# input_pull_up.net
KiCad netlist of a schematic drawn in EAGLE
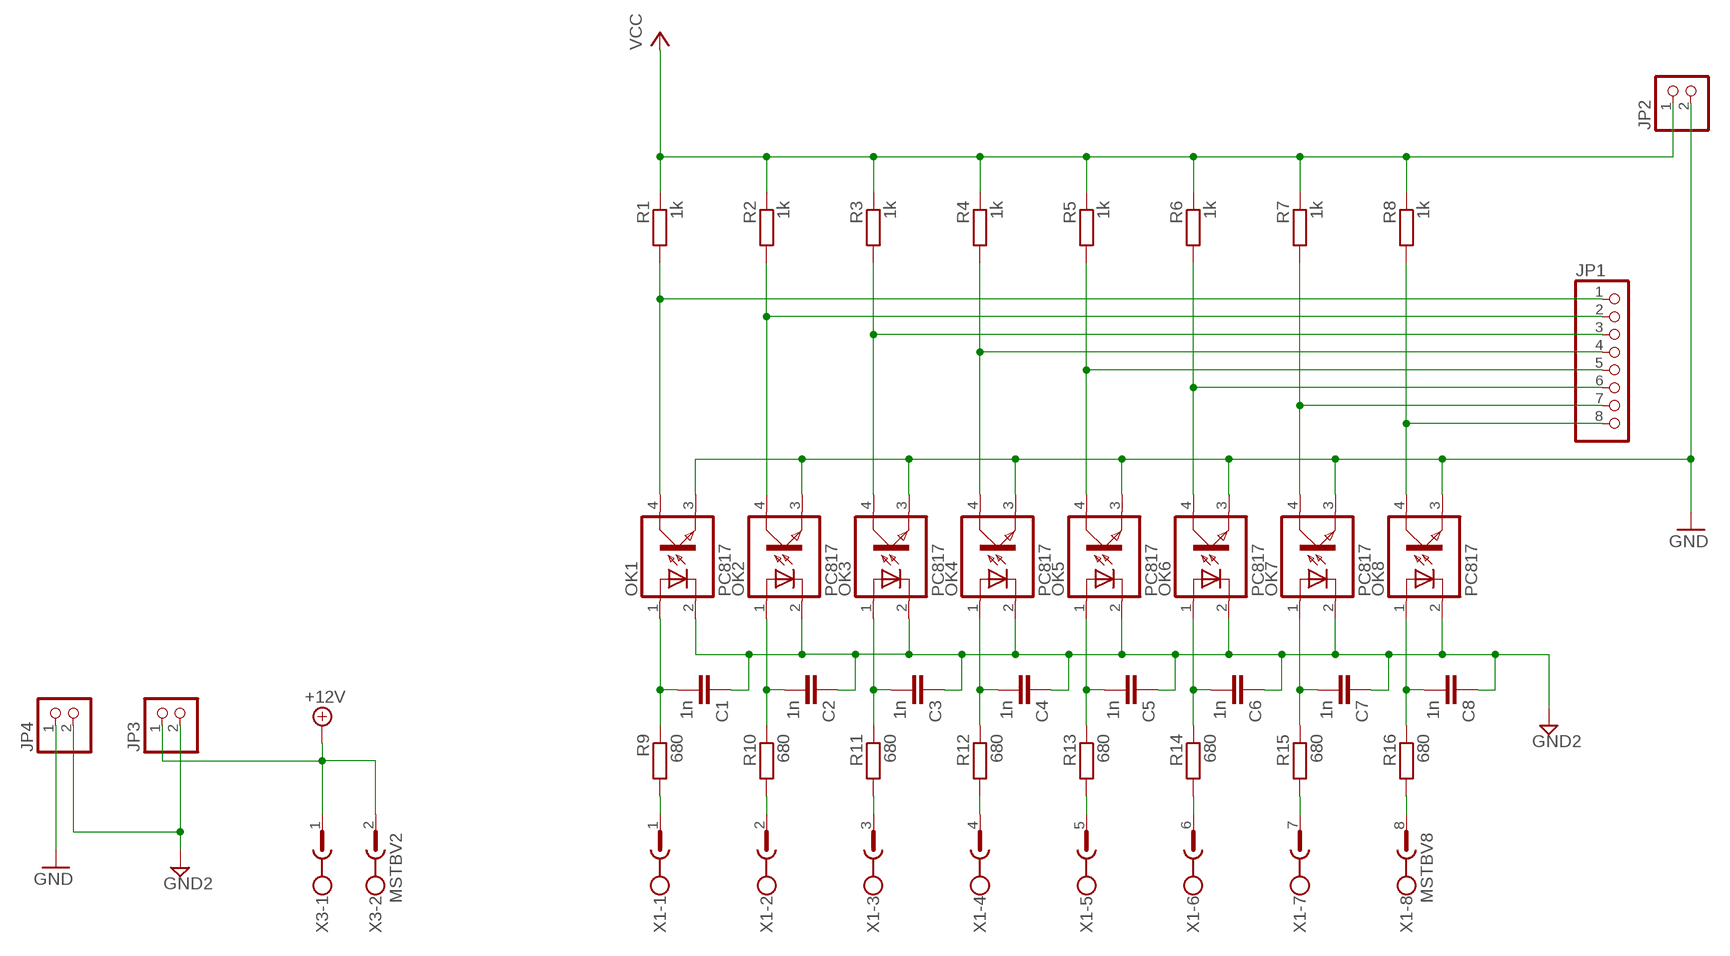
[diagram p0: schematic, sheet 1]

(export (version "E")
  (design (tool "Eeschema 10.0.6"))
  (components
    (comp (ref "C1")
      (value "1n")
      (footprint "eagle-import:C050-025X075")
      (libsource (lib "eagle-import") (part "C-EU050-025X075"))
    )
    (comp (ref "C2")
      (value "1n")
      (footprint "eagle-import:C050-025X075")
      (libsource (lib "eagle-import") (part "C-EU050-025X075"))
    )
    (comp (ref "C3")
      (value "1n")
      (footprint "eagle-import:C050-025X075")
      (libsource (lib "eagle-import") (part "C-EU050-025X075"))
    )
    (comp (ref "C4")
      (value "1n")
      (footprint "eagle-import:C050-025X075")
      (libsource (lib "eagle-import") (part "C-EU050-025X075"))
    )
    (comp (ref "C5")
      (value "1n")
      (footprint "eagle-import:C050-025X075")
      (libsource (lib "eagle-import") (part "C-EU050-025X075"))
    )
    (comp (ref "C6")
      (value "1n")
      (footprint "eagle-import:C050-025X075")
      (libsource (lib "eagle-import") (part "C-EU050-025X075"))
    )
    (comp (ref "C7")
      (value "1n")
      (footprint "eagle-import:C050-025X075")
      (libsource (lib "eagle-import") (part "C-EU050-025X075"))
    )
    (comp (ref "C8")
      (value "1n")
      (footprint "eagle-import:C050-025X075")
      (libsource (lib "eagle-import") (part "C-EU050-025X075"))
    )
    (comp (ref "JP1")
      (value "PINHD-1X8")
      (footprint "eagle-import:1X08")
      (libsource (lib "eagle-import") (part "PINHD-1X8"))
    )
    (comp (ref "JP2")
      (value "PINHD-1X2")
      (footprint "eagle-import:1X02")
      (libsource (lib "eagle-import") (part "PINHD-1X2"))
    )
    (comp (ref "JP3")
      (value "PINHD-1X2")
      (footprint "eagle-import:1X02")
      (libsource (lib "eagle-import") (part "PINHD-1X2"))
    )
    (comp (ref "JP4")
      (value "PINHD-1X2")
      (footprint "eagle-import:1X02")
      (libsource (lib "eagle-import") (part "PINHD-1X2"))
    )
    (comp (ref "OK1")
      (value "PC817")
      (footprint "eagle-import:DIL04")
      (fields (field (name "MPN") "PC817X4J000F"))
      (libsource (lib "eagle-import") (part "PC817"))
    )
    (comp (ref "OK2")
      (value "PC817")
      (footprint "eagle-import:DIL04")
      (fields (field (name "MPN") "PC817X4J000F"))
      (libsource (lib "eagle-import") (part "PC817"))
    )
    (comp (ref "OK3")
      (value "PC817")
      (footprint "eagle-import:DIL04")
      (fields (field (name "MPN") "PC817X4J000F"))
      (libsource (lib "eagle-import") (part "PC817"))
    )
    (comp (ref "OK4")
      (value "PC817")
      (footprint "eagle-import:DIL04")
      (fields (field (name "MPN") "PC817X4J000F"))
      (libsource (lib "eagle-import") (part "PC817"))
    )
    (comp (ref "OK5")
      (value "PC817")
      (footprint "eagle-import:DIL04")
      (fields (field (name "MPN") "PC817X4J000F"))
      (libsource (lib "eagle-import") (part "PC817"))
    )
    (comp (ref "OK6")
      (value "PC817")
      (footprint "eagle-import:DIL04")
      (fields (field (name "MPN") "PC817X4J000F"))
      (libsource (lib "eagle-import") (part "PC817"))
    )
    (comp (ref "OK7")
      (value "PC817")
      (footprint "eagle-import:DIL04")
      (fields (field (name "MPN") "PC817X4J000F"))
      (libsource (lib "eagle-import") (part "PC817"))
    )
    (comp (ref "OK8")
      (value "PC817")
      (footprint "eagle-import:DIL04")
      (fields (field (name "MPN") "PC817X4J000F"))
      (libsource (lib "eagle-import") (part "PC817"))
    )
    (comp (ref "R1")
      (value "1k")
      (footprint "eagle-import:0204_7")
      (libsource (lib "eagle-import") (part "R-EU_0204/7"))
    )
    (comp (ref "R2")
      (value "1k")
      (footprint "eagle-import:0204_7")
      (libsource (lib "eagle-import") (part "R-EU_0204/7"))
    )
    (comp (ref "R3")
      (value "1k")
      (footprint "eagle-import:0204_7")
      (libsource (lib "eagle-import") (part "R-EU_0204/7"))
    )
    (comp (ref "R4")
      (value "1k")
      (footprint "eagle-import:0204_7")
      (libsource (lib "eagle-import") (part "R-EU_0204/7"))
    )
    (comp (ref "R5")
      (value "1k")
      (footprint "eagle-import:0204_7")
      (libsource (lib "eagle-import") (part "R-EU_0204/7"))
    )
    (comp (ref "R6")
      (value "1k")
      (footprint "eagle-import:0204_7")
      (libsource (lib "eagle-import") (part "R-EU_0204/7"))
    )
    (comp (ref "R7")
      (value "1k")
      (footprint "eagle-import:0204_7")
      (libsource (lib "eagle-import") (part "R-EU_0204/7"))
    )
    (comp (ref "R8")
      (value "1k")
      (footprint "eagle-import:0204_7")
      (libsource (lib "eagle-import") (part "R-EU_0204/7"))
    )
    (comp (ref "R9")
      (value "680")
      (footprint "eagle-import:0204_7")
      (libsource (lib "eagle-import") (part "R-EU_0204/7"))
    )
    (comp (ref "R10")
      (value "680")
      (footprint "eagle-import:0204_7")
      (libsource (lib "eagle-import") (part "R-EU_0204/7"))
    )
    (comp (ref "R11")
      (value "680")
      (footprint "eagle-import:0204_7")
      (libsource (lib "eagle-import") (part "R-EU_0204/7"))
    )
    (comp (ref "R12")
      (value "680")
      (footprint "eagle-import:0204_7")
      (libsource (lib "eagle-import") (part "R-EU_0204/7"))
    )
    (comp (ref "R13")
      (value "680")
      (footprint "eagle-import:0204_7")
      (libsource (lib "eagle-import") (part "R-EU_0204/7"))
    )
    (comp (ref "R14")
      (value "680")
      (footprint "eagle-import:0204_7")
      (libsource (lib "eagle-import") (part "R-EU_0204/7"))
    )
    (comp (ref "R15")
      (value "680")
      (footprint "eagle-import:0204_7")
      (libsource (lib "eagle-import") (part "R-EU_0204/7"))
    )
    (comp (ref "R16")
      (value "680")
      (footprint "eagle-import:0204_7")
      (libsource (lib "eagle-import") (part "R-EU_0204/7"))
    )
    (comp (ref "X1")
      (value "MSTBV8")
      (footprint "eagle-import:MSTBV8")
      (libsource (lib "eagle-import") (part "MSTBV8"))
    )
    (comp (ref "X3")
      (value "MSTBV2")
      (footprint "eagle-import:MSTBV2")
      (libsource (lib "eagle-import") (part "MSTBV2"))
    )
  )
  (nets
    (net (code "1") (name "+12V") (class "Default")
      (node (ref "JP3") (pin "1") (pinfunction "1_1") (pintype "passive"))
      (node (ref "X3") (pin "1") (pinfunction "1_1") (pintype "passive"))
      (node (ref "X3") (pin "2") (pinfunction "1_2") (pintype "passive"))
    )
    (net (code "2") (name "GND") (class "Default")
      (node (ref "JP2") (pin "2") (pinfunction "2_2") (pintype "passive"))
      (node (ref "JP4") (pin "1") (pinfunction "1_1") (pintype "passive"))
      (node (ref "OK1") (pin "3") (pinfunction "EMIT_3") (pintype "passive"))
      (node (ref "OK2") (pin "3") (pinfunction "EMIT_3") (pintype "passive"))
      (node (ref "OK3") (pin "3") (pinfunction "EMIT_3") (pintype "passive"))
      (node (ref "OK4") (pin "3") (pinfunction "EMIT_3") (pintype "passive"))
      (node (ref "OK5") (pin "3") (pinfunction "EMIT_3") (pintype "passive"))
      (node (ref "OK6") (pin "3") (pinfunction "EMIT_3") (pintype "passive"))
      (node (ref "OK7") (pin "3") (pinfunction "EMIT_3") (pintype "passive"))
      (node (ref "OK8") (pin "3") (pinfunction "EMIT_3") (pintype "passive"))
    )
    (net (code "3") (name "GND2") (class "Default")
      (node (ref "C1") (pin "1") (pinfunction "1_1") (pintype "passive"))
      (node (ref "C2") (pin "1") (pinfunction "1_1") (pintype "passive"))
      (node (ref "C3") (pin "1") (pinfunction "1_1") (pintype "passive"))
      (node (ref "C4") (pin "1") (pinfunction "1_1") (pintype "passive"))
      (node (ref "C5") (pin "1") (pinfunction "1_1") (pintype "passive"))
      (node (ref "C6") (pin "1") (pinfunction "1_1") (pintype "passive"))
      (node (ref "C7") (pin "1") (pinfunction "1_1") (pintype "passive"))
      (node (ref "C8") (pin "1") (pinfunction "1_1") (pintype "passive"))
      (node (ref "JP3") (pin "2") (pinfunction "2_2") (pintype "passive"))
      (node (ref "JP4") (pin "2") (pinfunction "2_2") (pintype "passive"))
      (node (ref "OK1") (pin "2") (pinfunction "C_2") (pintype "passive"))
      (node (ref "OK2") (pin "2") (pinfunction "C_2") (pintype "passive"))
      (node (ref "OK3") (pin "2") (pinfunction "C_2") (pintype "passive"))
      (node (ref "OK4") (pin "2") (pinfunction "C_2") (pintype "passive"))
      (node (ref "OK5") (pin "2") (pinfunction "C_2") (pintype "passive"))
      (node (ref "OK6") (pin "2") (pinfunction "C_2") (pintype "passive"))
      (node (ref "OK7") (pin "2") (pinfunction "C_2") (pintype "passive"))
      (node (ref "OK8") (pin "2") (pinfunction "C_2") (pintype "passive"))
    )
    (net (code "4") (name "Net-(OK1-A)") (class "Default")
      (node (ref "C1") (pin "2") (pinfunction "2_2") (pintype "passive"))
      (node (ref "OK1") (pin "1") (pinfunction "A_1") (pintype "passive"))
      (node (ref "R9") (pin "1") (pinfunction "1_1") (pintype "passive"))
    )
    (net (code "5") (name "Net-(OK1-COL)") (class "Default")
      (node (ref "JP1") (pin "1") (pinfunction "1_1") (pintype "passive"))
      (node (ref "OK1") (pin "4") (pinfunction "COL_4") (pintype "passive"))
      (node (ref "R1") (pin "2") (pinfunction "2_2") (pintype "passive"))
    )
    (net (code "6") (name "Net-(OK2-A)") (class "Default")
      (node (ref "C2") (pin "2") (pinfunction "2_2") (pintype "passive"))
      (node (ref "OK2") (pin "1") (pinfunction "A_1") (pintype "passive"))
      (node (ref "R10") (pin "1") (pinfunction "1_1") (pintype "passive"))
    )
    (net (code "7") (name "Net-(OK2-COL)") (class "Default")
      (node (ref "JP1") (pin "2") (pinfunction "2_2") (pintype "passive"))
      (node (ref "OK2") (pin "4") (pinfunction "COL_4") (pintype "passive"))
      (node (ref "R2") (pin "2") (pinfunction "2_2") (pintype "passive"))
    )
    (net (code "8") (name "Net-(OK3-A)") (class "Default")
      (node (ref "C3") (pin "2") (pinfunction "2_2") (pintype "passive"))
      (node (ref "OK3") (pin "1") (pinfunction "A_1") (pintype "passive"))
      (node (ref "R11") (pin "1") (pinfunction "1_1") (pintype "passive"))
    )
    (net (code "9") (name "Net-(OK3-COL)") (class "Default")
      (node (ref "JP1") (pin "3") (pinfunction "3_3") (pintype "passive"))
      (node (ref "OK3") (pin "4") (pinfunction "COL_4") (pintype "passive"))
      (node (ref "R3") (pin "2") (pinfunction "2_2") (pintype "passive"))
    )
    (net (code "10") (name "Net-(OK4-A)") (class "Default")
      (node (ref "C4") (pin "2") (pinfunction "2_2") (pintype "passive"))
      (node (ref "OK4") (pin "1") (pinfunction "A_1") (pintype "passive"))
      (node (ref "R12") (pin "1") (pinfunction "1_1") (pintype "passive"))
    )
    (net (code "11") (name "Net-(OK4-COL)") (class "Default")
      (node (ref "JP1") (pin "4") (pinfunction "4_4") (pintype "passive"))
      (node (ref "OK4") (pin "4") (pinfunction "COL_4") (pintype "passive"))
      (node (ref "R4") (pin "2") (pinfunction "2_2") (pintype "passive"))
    )
    (net (code "12") (name "Net-(OK5-A)") (class "Default")
      (node (ref "C5") (pin "2") (pinfunction "2_2") (pintype "passive"))
      (node (ref "OK5") (pin "1") (pinfunction "A_1") (pintype "passive"))
      (node (ref "R13") (pin "1") (pinfunction "1_1") (pintype "passive"))
    )
    (net (code "13") (name "Net-(OK5-COL)") (class "Default")
      (node (ref "JP1") (pin "5") (pinfunction "5_5") (pintype "passive"))
      (node (ref "OK5") (pin "4") (pinfunction "COL_4") (pintype "passive"))
      (node (ref "R5") (pin "2") (pinfunction "2_2") (pintype "passive"))
    )
    (net (code "14") (name "Net-(OK6-A)") (class "Default")
      (node (ref "C6") (pin "2") (pinfunction "2_2") (pintype "passive"))
      (node (ref "OK6") (pin "1") (pinfunction "A_1") (pintype "passive"))
      (node (ref "R14") (pin "1") (pinfunction "1_1") (pintype "passive"))
    )
    (net (code "15") (name "Net-(OK6-COL)") (class "Default")
      (node (ref "JP1") (pin "6") (pinfunction "6_6") (pintype "passive"))
      (node (ref "OK6") (pin "4") (pinfunction "COL_4") (pintype "passive"))
      (node (ref "R6") (pin "2") (pinfunction "2_2") (pintype "passive"))
    )
    (net (code "16") (name "Net-(OK7-A)") (class "Default")
      (node (ref "C7") (pin "2") (pinfunction "2_2") (pintype "passive"))
      (node (ref "OK7") (pin "1") (pinfunction "A_1") (pintype "passive"))
      (node (ref "R15") (pin "1") (pinfunction "1_1") (pintype "passive"))
    )
    (net (code "17") (name "Net-(OK7-COL)") (class "Default")
      (node (ref "JP1") (pin "7") (pinfunction "7_7") (pintype "passive"))
      (node (ref "OK7") (pin "4") (pinfunction "COL_4") (pintype "passive"))
      (node (ref "R7") (pin "2") (pinfunction "2_2") (pintype "passive"))
    )
    (net (code "18") (name "Net-(OK8-A)") (class "Default")
      (node (ref "C8") (pin "2") (pinfunction "2_2") (pintype "passive"))
      (node (ref "OK8") (pin "1") (pinfunction "A_1") (pintype "passive"))
      (node (ref "R16") (pin "1") (pinfunction "1_1") (pintype "passive"))
    )
    (net (code "19") (name "Net-(OK8-COL)") (class "Default")
      (node (ref "JP1") (pin "8") (pinfunction "8_8") (pintype "passive"))
      (node (ref "OK8") (pin "4") (pinfunction "COL_4") (pintype "passive"))
      (node (ref "R8") (pin "2") (pinfunction "2_2") (pintype "passive"))
    )
    (net (code "20") (name "Net-(R9-Pad2)") (class "Default")
      (node (ref "R9") (pin "2") (pinfunction "2_2") (pintype "passive"))
      (node (ref "X1") (pin "1") (pinfunction "1_1") (pintype "passive"))
    )
    (net (code "21") (name "Net-(X1B-1)") (class "Default")
      (node (ref "R10") (pin "2") (pinfunction "2_2") (pintype "passive"))
      (node (ref "X1") (pin "2") (pinfunction "1_2") (pintype "passive"))
    )
    (net (code "22") (name "Net-(X1C-1)") (class "Default")
      (node (ref "R11") (pin "2") (pinfunction "2_2") (pintype "passive"))
      (node (ref "X1") (pin "3") (pinfunction "1_3") (pintype "passive"))
    )
    (net (code "23") (name "Net-(X1D-1)") (class "Default")
      (node (ref "R12") (pin "2") (pinfunction "2_2") (pintype "passive"))
      (node (ref "X1") (pin "4") (pinfunction "1_4") (pintype "passive"))
    )
    (net (code "24") (name "Net-(X1E-1)") (class "Default")
      (node (ref "R13") (pin "2") (pinfunction "2_2") (pintype "passive"))
      (node (ref "X1") (pin "5") (pinfunction "1_5") (pintype "passive"))
    )
    (net (code "25") (name "Net-(X1F-1)") (class "Default")
      (node (ref "R14") (pin "2") (pinfunction "2_2") (pintype "passive"))
      (node (ref "X1") (pin "6") (pinfunction "1_6") (pintype "passive"))
    )
    (net (code "26") (name "Net-(X1G-1)") (class "Default")
      (node (ref "R15") (pin "2") (pinfunction "2_2") (pintype "passive"))
      (node (ref "X1") (pin "7") (pinfunction "1_7") (pintype "passive"))
    )
    (net (code "27") (name "Net-(X1H-1)") (class "Default")
      (node (ref "R16") (pin "2") (pinfunction "2_2") (pintype "passive"))
      (node (ref "X1") (pin "8") (pinfunction "1_8") (pintype "passive"))
    )
    (net (code "28") (name "VCC") (class "Default")
      (node (ref "JP2") (pin "1") (pinfunction "1_1") (pintype "passive"))
      (node (ref "R1") (pin "1") (pinfunction "1_1") (pintype "passive"))
      (node (ref "R2") (pin "1") (pinfunction "1_1") (pintype "passive"))
      (node (ref "R3") (pin "1") (pinfunction "1_1") (pintype "passive"))
      (node (ref "R4") (pin "1") (pinfunction "1_1") (pintype "passive"))
      (node (ref "R5") (pin "1") (pinfunction "1_1") (pintype "passive"))
      (node (ref "R6") (pin "1") (pinfunction "1_1") (pintype "passive"))
      (node (ref "R7") (pin "1") (pinfunction "1_1") (pintype "passive"))
      (node (ref "R8") (pin "1") (pinfunction "1_1") (pintype "passive"))
    )
  )
)
